# main.net
KiCad netlist of a schematic drawn in Altium Designer
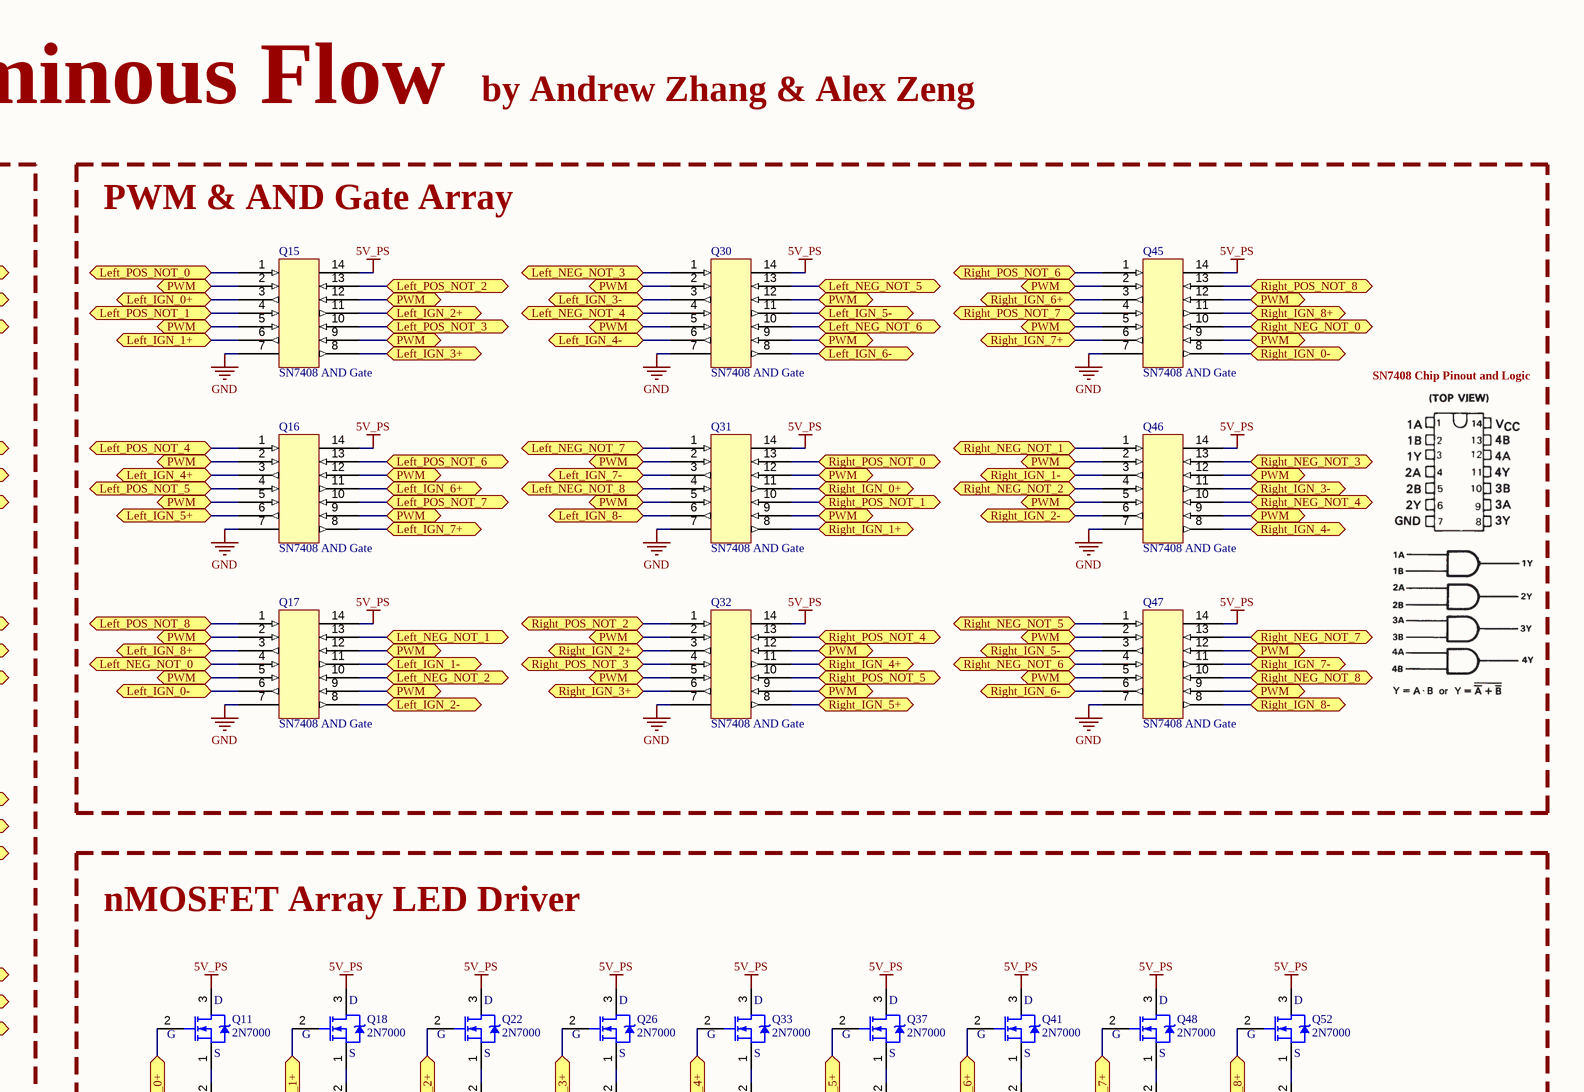
[diagram p0: main.SchDoc, top right]
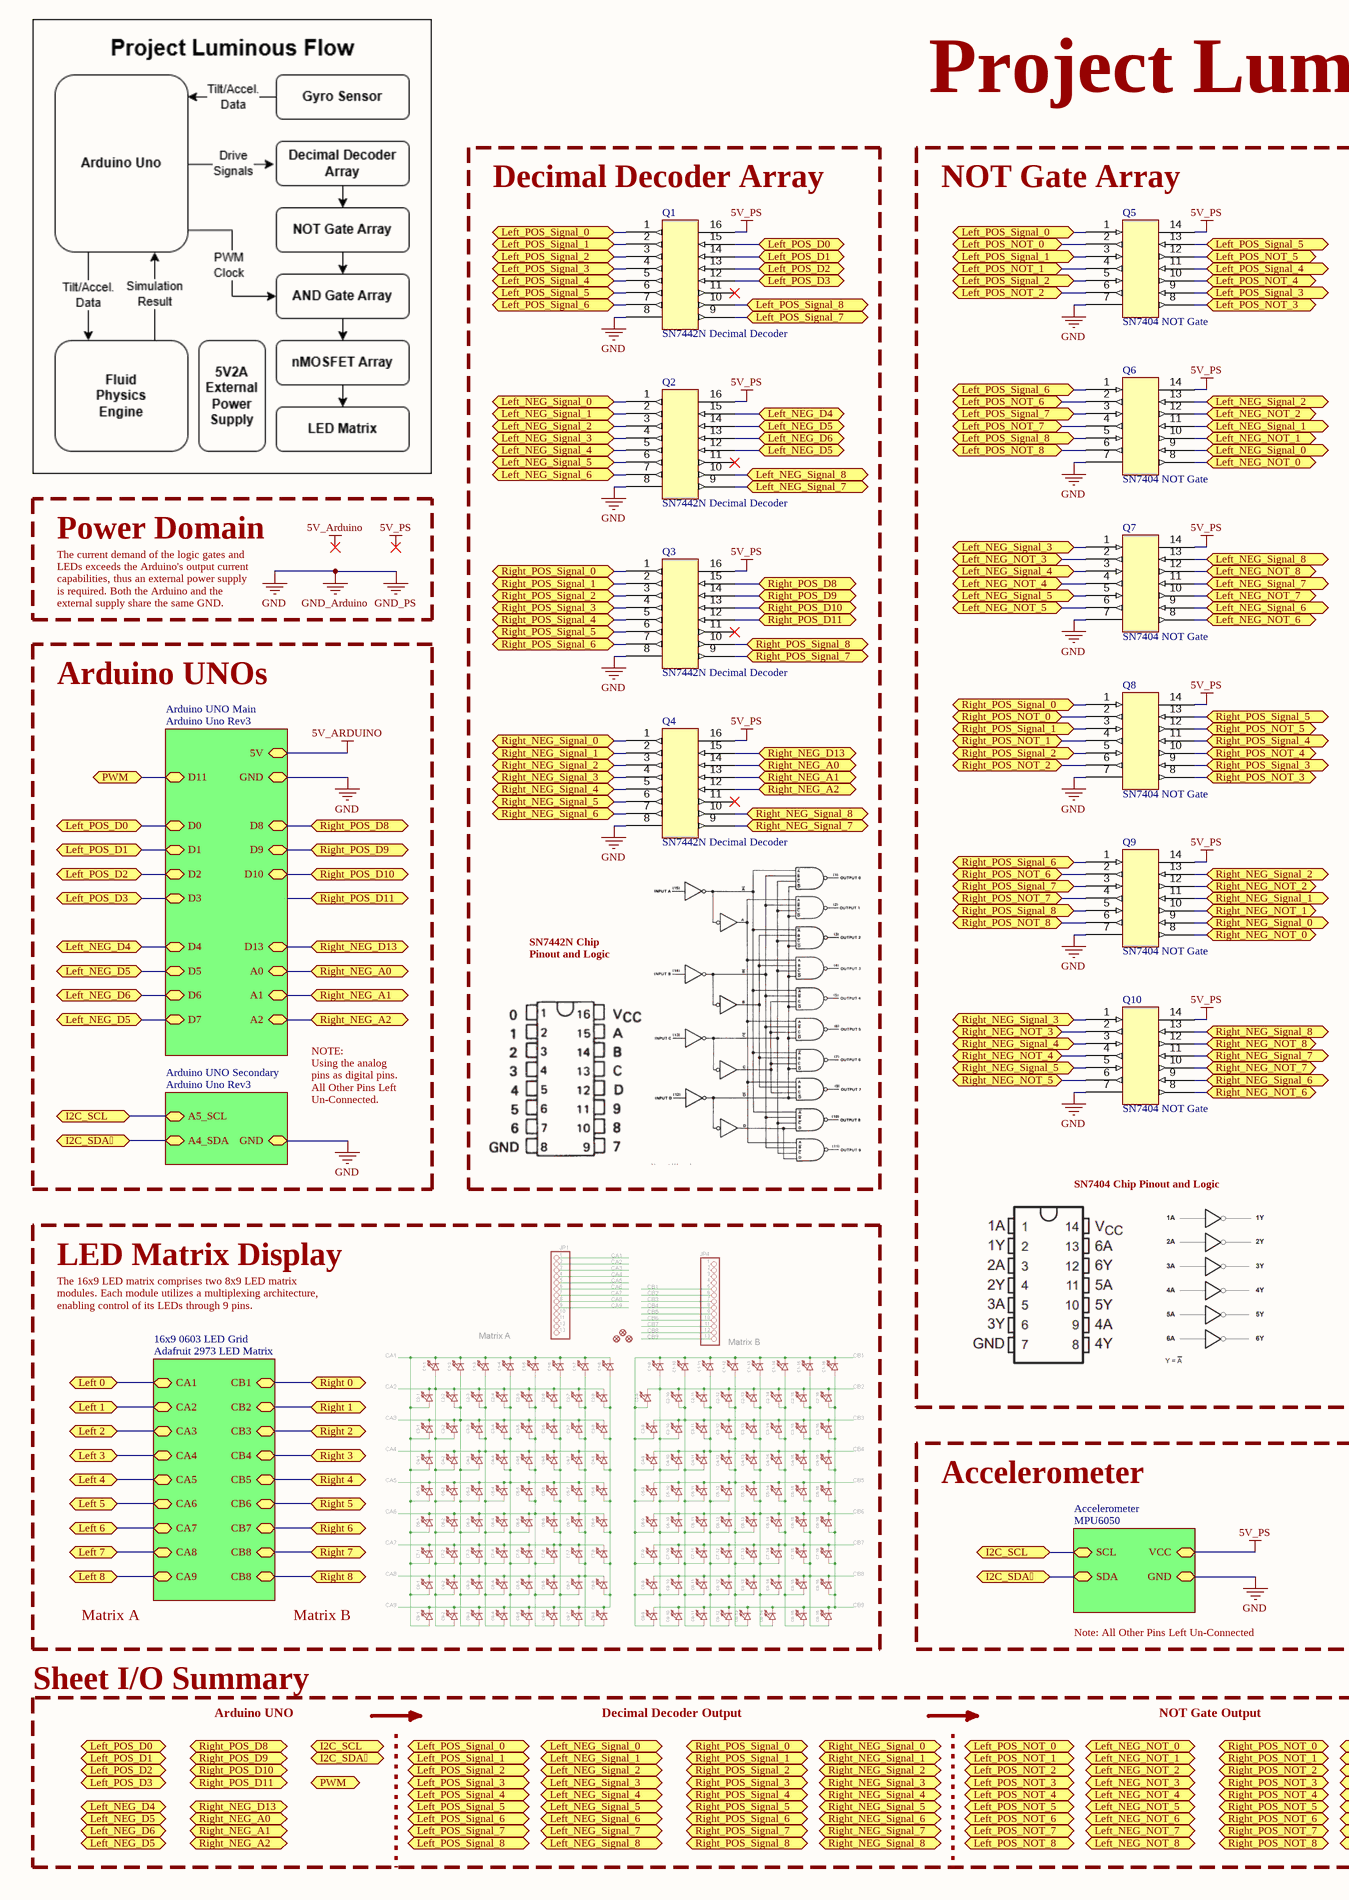
[diagram p1: main.SchDoc, bottom left]
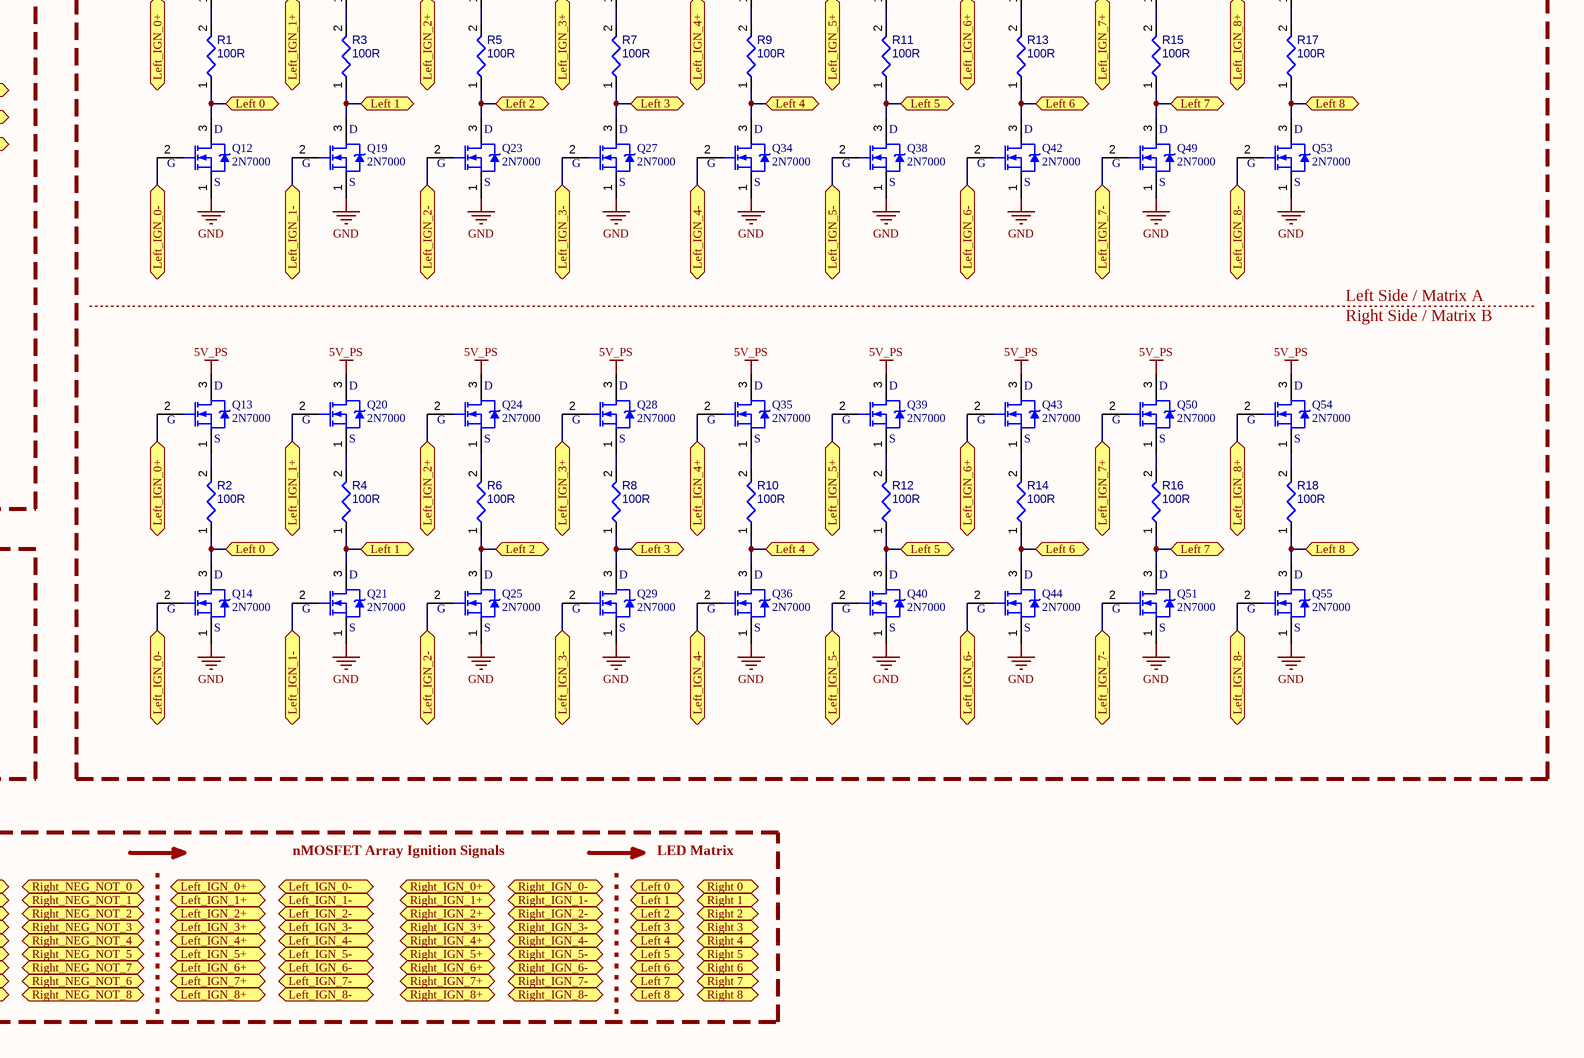
[diagram p2: main.SchDoc, bottom right]

(export (version "E")
  (design (tool "Eeschema 10.0.6"))
  (components
    (comp (ref "Q1")
      (value "SN7442N Decimal Decoder")
      (description "10-line Decimal Decoder")
      (libsource (lib "OTGRP") (part "SN7442N"))
    )
    (comp (ref "Q2")
      (value "SN7442N Decimal Decoder")
      (description "10-line Decimal Decoder")
      (libsource (lib "OTGRP") (part "SN7442N"))
    )
    (comp (ref "Q3")
      (value "SN7442N Decimal Decoder")
      (description "10-line Decimal Decoder")
      (libsource (lib "OTGRP") (part "SN7442N"))
    )
    (comp (ref "Q4")
      (value "SN7442N Decimal Decoder")
      (description "10-line Decimal Decoder")
      (libsource (lib "OTGRP") (part "SN7442N"))
    )
    (comp (ref "Q5") (value "SN7404 NOT Gate") (libsource (lib "OTGRP") (part "SN7404 NOT Gate")))
    (comp (ref "Q6") (value "SN7404 NOT Gate") (libsource (lib "OTGRP") (part "SN7404 NOT Gate")))
    (comp (ref "Q7") (value "SN7404 NOT Gate") (libsource (lib "OTGRP") (part "SN7404 NOT Gate")))
    (comp (ref "Q8") (value "SN7404 NOT Gate") (libsource (lib "OTGRP") (part "SN7404 NOT Gate")))
    (comp (ref "Q9") (value "SN7404 NOT Gate") (libsource (lib "OTGRP") (part "SN7404 NOT Gate")))
    (comp (ref "Q10") (value "SN7404 NOT Gate") (libsource (lib "OTGRP") (part "SN7404 NOT Gate")))
    (comp (ref "Q11")
      (value "2N7000")
      (footprint "ONSC-TO-92-3-29-11_AM_BL")
      (description "Small Signal MOSFET, 200 mA, 60 V, N-Channel, 3-Pin TO-92, Bulk Box")
      (fields (field (name "POWER") "400mW") (field (name "MANUFACTURER") "Fairchild Semiconductor"))
      (libsource (lib "OTGRP") (part "ONSC-NMOS-S1G2D3-3"))
    )
    (comp (ref "Q12")
      (value "2N7000")
      (footprint "ONSC-TO-92-3-29-11_AM_BL")
      (description "Small Signal MOSFET, 200 mA, 60 V, N-Channel, 3-Pin TO-92, Bulk Box")
      (fields (field (name "POWER") "400mW") (field (name "MANUFACTURER") "Fairchild Semiconductor"))
      (libsource (lib "OTGRP") (part "ONSC-NMOS-S1G2D3-3"))
    )
    (comp (ref "Q13")
      (value "2N7000")
      (footprint "ONSC-TO-92-3-29-11_AM_BL")
      (description "Small Signal MOSFET, 200 mA, 60 V, N-Channel, 3-Pin TO-92, Bulk Box")
      (fields (field (name "POWER") "400mW") (field (name "MANUFACTURER") "Fairchild Semiconductor"))
      (libsource (lib "OTGRP") (part "ONSC-NMOS-S1G2D3-3"))
    )
    (comp (ref "Q14")
      (value "2N7000")
      (footprint "ONSC-TO-92-3-29-11_AM_BL")
      (description "Small Signal MOSFET, 200 mA, 60 V, N-Channel, 3-Pin TO-92, Bulk Box")
      (fields (field (name "POWER") "400mW") (field (name "MANUFACTURER") "Fairchild Semiconductor"))
      (libsource (lib "OTGRP") (part "ONSC-NMOS-S1G2D3-3"))
    )
    (comp (ref "Q15")
      (value "SN7408 AND Gate")
      (description "Quad 2-input Positive-AND gates 14-PDIP 0 to 70")
      (libsource (lib "OTGRP") (part "SN7408"))
    )
    (comp (ref "Q16")
      (value "SN7408 AND Gate")
      (description "Quad 2-input Positive-AND gates 14-PDIP 0 to 70")
      (libsource (lib "OTGRP") (part "SN7408"))
    )
    (comp (ref "Q17")
      (value "SN7408 AND Gate")
      (description "Quad 2-input Positive-AND gates 14-PDIP 0 to 70")
      (libsource (lib "OTGRP") (part "SN7408"))
    )
    (comp (ref "Q18")
      (value "2N7000")
      (footprint "ONSC-TO-92-3-29-11_AM_BL")
      (description "Small Signal MOSFET, 200 mA, 60 V, N-Channel, 3-Pin TO-92, Bulk Box")
      (fields (field (name "POWER") "400mW") (field (name "MANUFACTURER") "Fairchild Semiconductor"))
      (libsource (lib "OTGRP") (part "ONSC-NMOS-S1G2D3-3"))
    )
    (comp (ref "Q19")
      (value "2N7000")
      (footprint "ONSC-TO-92-3-29-11_AM_BL")
      (description "Small Signal MOSFET, 200 mA, 60 V, N-Channel, 3-Pin TO-92, Bulk Box")
      (fields (field (name "POWER") "400mW") (field (name "MANUFACTURER") "Fairchild Semiconductor"))
      (libsource (lib "OTGRP") (part "ONSC-NMOS-S1G2D3-3"))
    )
    (comp (ref "Q20")
      (value "2N7000")
      (footprint "ONSC-TO-92-3-29-11_AM_BL")
      (description "Small Signal MOSFET, 200 mA, 60 V, N-Channel, 3-Pin TO-92, Bulk Box")
      (fields (field (name "POWER") "400mW") (field (name "MANUFACTURER") "Fairchild Semiconductor"))
      (libsource (lib "OTGRP") (part "ONSC-NMOS-S1G2D3-3"))
    )
    (comp (ref "Q21")
      (value "2N7000")
      (footprint "ONSC-TO-92-3-29-11_AM_BL")
      (description "Small Signal MOSFET, 200 mA, 60 V, N-Channel, 3-Pin TO-92, Bulk Box")
      (fields (field (name "POWER") "400mW") (field (name "MANUFACTURER") "Fairchild Semiconductor"))
      (libsource (lib "OTGRP") (part "ONSC-NMOS-S1G2D3-3"))
    )
    (comp (ref "Q22")
      (value "2N7000")
      (footprint "ONSC-TO-92-3-29-11_AM_BL")
      (description "Small Signal MOSFET, 200 mA, 60 V, N-Channel, 3-Pin TO-92, Bulk Box")
      (fields (field (name "POWER") "400mW") (field (name "MANUFACTURER") "Fairchild Semiconductor"))
      (libsource (lib "OTGRP") (part "ONSC-NMOS-S1G2D3-3"))
    )
    (comp (ref "Q23")
      (value "2N7000")
      (footprint "ONSC-TO-92-3-29-11_AM_BL")
      (description "Small Signal MOSFET, 200 mA, 60 V, N-Channel, 3-Pin TO-92, Bulk Box")
      (fields (field (name "POWER") "400mW") (field (name "MANUFACTURER") "Fairchild Semiconductor"))
      (libsource (lib "OTGRP") (part "ONSC-NMOS-S1G2D3-3"))
    )
    (comp (ref "Q24")
      (value "2N7000")
      (footprint "ONSC-TO-92-3-29-11_AM_BL")
      (description "Small Signal MOSFET, 200 mA, 60 V, N-Channel, 3-Pin TO-92, Bulk Box")
      (fields (field (name "POWER") "400mW") (field (name "MANUFACTURER") "Fairchild Semiconductor"))
      (libsource (lib "OTGRP") (part "ONSC-NMOS-S1G2D3-3"))
    )
    (comp (ref "Q25")
      (value "2N7000")
      (footprint "ONSC-TO-92-3-29-11_AM_BL")
      (description "Small Signal MOSFET, 200 mA, 60 V, N-Channel, 3-Pin TO-92, Bulk Box")
      (fields (field (name "POWER") "400mW") (field (name "MANUFACTURER") "Fairchild Semiconductor"))
      (libsource (lib "OTGRP") (part "ONSC-NMOS-S1G2D3-3"))
    )
    (comp (ref "Q26")
      (value "2N7000")
      (footprint "ONSC-TO-92-3-29-11_AM_BL")
      (description "Small Signal MOSFET, 200 mA, 60 V, N-Channel, 3-Pin TO-92, Bulk Box")
      (fields (field (name "POWER") "400mW") (field (name "MANUFACTURER") "Fairchild Semiconductor"))
      (libsource (lib "OTGRP") (part "ONSC-NMOS-S1G2D3-3"))
    )
    (comp (ref "Q27")
      (value "2N7000")
      (footprint "ONSC-TO-92-3-29-11_AM_BL")
      (description "Small Signal MOSFET, 200 mA, 60 V, N-Channel, 3-Pin TO-92, Bulk Box")
      (fields (field (name "POWER") "400mW") (field (name "MANUFACTURER") "Fairchild Semiconductor"))
      (libsource (lib "OTGRP") (part "ONSC-NMOS-S1G2D3-3"))
    )
    (comp (ref "Q28")
      (value "2N7000")
      (footprint "ONSC-TO-92-3-29-11_AM_BL")
      (description "Small Signal MOSFET, 200 mA, 60 V, N-Channel, 3-Pin TO-92, Bulk Box")
      (fields (field (name "POWER") "400mW") (field (name "MANUFACTURER") "Fairchild Semiconductor"))
      (libsource (lib "OTGRP") (part "ONSC-NMOS-S1G2D3-3"))
    )
    (comp (ref "Q29")
      (value "2N7000")
      (footprint "ONSC-TO-92-3-29-11_AM_BL")
      (description "Small Signal MOSFET, 200 mA, 60 V, N-Channel, 3-Pin TO-92, Bulk Box")
      (fields (field (name "POWER") "400mW") (field (name "MANUFACTURER") "Fairchild Semiconductor"))
      (libsource (lib "OTGRP") (part "ONSC-NMOS-S1G2D3-3"))
    )
    (comp (ref "Q30")
      (value "SN7408 AND Gate")
      (description "Quad 2-input Positive-AND gates 14-PDIP 0 to 70")
      (libsource (lib "OTGRP") (part "SN7408"))
    )
    (comp (ref "Q31")
      (value "SN7408 AND Gate")
      (description "Quad 2-input Positive-AND gates 14-PDIP 0 to 70")
      (libsource (lib "OTGRP") (part "SN7408"))
    )
    (comp (ref "Q32")
      (value "SN7408 AND Gate")
      (description "Quad 2-input Positive-AND gates 14-PDIP 0 to 70")
      (libsource (lib "OTGRP") (part "SN7408"))
    )
    (comp (ref "Q33")
      (value "2N7000")
      (footprint "ONSC-TO-92-3-29-11_AM_BL")
      (description "Small Signal MOSFET, 200 mA, 60 V, N-Channel, 3-Pin TO-92, Bulk Box")
      (fields (field (name "POWER") "400mW") (field (name "MANUFACTURER") "Fairchild Semiconductor"))
      (libsource (lib "OTGRP") (part "ONSC-NMOS-S1G2D3-3"))
    )
    (comp (ref "Q34")
      (value "2N7000")
      (footprint "ONSC-TO-92-3-29-11_AM_BL")
      (description "Small Signal MOSFET, 200 mA, 60 V, N-Channel, 3-Pin TO-92, Bulk Box")
      (fields (field (name "POWER") "400mW") (field (name "MANUFACTURER") "Fairchild Semiconductor"))
      (libsource (lib "OTGRP") (part "ONSC-NMOS-S1G2D3-3"))
    )
    (comp (ref "Q35")
      (value "2N7000")
      (footprint "ONSC-TO-92-3-29-11_AM_BL")
      (description "Small Signal MOSFET, 200 mA, 60 V, N-Channel, 3-Pin TO-92, Bulk Box")
      (fields (field (name "POWER") "400mW") (field (name "MANUFACTURER") "Fairchild Semiconductor"))
      (libsource (lib "OTGRP") (part "ONSC-NMOS-S1G2D3-3"))
    )
    (comp (ref "Q36")
      (value "2N7000")
      (footprint "ONSC-TO-92-3-29-11_AM_BL")
      (description "Small Signal MOSFET, 200 mA, 60 V, N-Channel, 3-Pin TO-92, Bulk Box")
      (fields (field (name "POWER") "400mW") (field (name "MANUFACTURER") "Fairchild Semiconductor"))
      (libsource (lib "OTGRP") (part "ONSC-NMOS-S1G2D3-3"))
    )
    (comp (ref "Q37")
      (value "2N7000")
      (footprint "ONSC-TO-92-3-29-11_AM_BL")
      (description "Small Signal MOSFET, 200 mA, 60 V, N-Channel, 3-Pin TO-92, Bulk Box")
      (fields (field (name "POWER") "400mW") (field (name "MANUFACTURER") "Fairchild Semiconductor"))
      (libsource (lib "OTGRP") (part "ONSC-NMOS-S1G2D3-3"))
    )
    (comp (ref "Q38")
      (value "2N7000")
      (footprint "ONSC-TO-92-3-29-11_AM_BL")
      (description "Small Signal MOSFET, 200 mA, 60 V, N-Channel, 3-Pin TO-92, Bulk Box")
      (fields (field (name "POWER") "400mW") (field (name "MANUFACTURER") "Fairchild Semiconductor"))
      (libsource (lib "OTGRP") (part "ONSC-NMOS-S1G2D3-3"))
    )
    (comp (ref "Q39")
      (value "2N7000")
      (footprint "ONSC-TO-92-3-29-11_AM_BL")
      (description "Small Signal MOSFET, 200 mA, 60 V, N-Channel, 3-Pin TO-92, Bulk Box")
      (fields (field (name "POWER") "400mW") (field (name "MANUFACTURER") "Fairchild Semiconductor"))
      (libsource (lib "OTGRP") (part "ONSC-NMOS-S1G2D3-3"))
    )
    (comp (ref "Q40")
      (value "2N7000")
      (footprint "ONSC-TO-92-3-29-11_AM_BL")
      (description "Small Signal MOSFET, 200 mA, 60 V, N-Channel, 3-Pin TO-92, Bulk Box")
      (fields (field (name "POWER") "400mW") (field (name "MANUFACTURER") "Fairchild Semiconductor"))
      (libsource (lib "OTGRP") (part "ONSC-NMOS-S1G2D3-3"))
    )
    (comp (ref "Q41")
      (value "2N7000")
      (footprint "ONSC-TO-92-3-29-11_AM_BL")
      (description "Small Signal MOSFET, 200 mA, 60 V, N-Channel, 3-Pin TO-92, Bulk Box")
      (fields (field (name "POWER") "400mW") (field (name "MANUFACTURER") "Fairchild Semiconductor"))
      (libsource (lib "OTGRP") (part "ONSC-NMOS-S1G2D3-3"))
    )
    (comp (ref "Q42")
      (value "2N7000")
      (footprint "ONSC-TO-92-3-29-11_AM_BL")
      (description "Small Signal MOSFET, 200 mA, 60 V, N-Channel, 3-Pin TO-92, Bulk Box")
      (fields (field (name "POWER") "400mW") (field (name "MANUFACTURER") "Fairchild Semiconductor"))
      (libsource (lib "OTGRP") (part "ONSC-NMOS-S1G2D3-3"))
    )
    (comp (ref "Q43")
      (value "2N7000")
      (footprint "ONSC-TO-92-3-29-11_AM_BL")
      (description "Small Signal MOSFET, 200 mA, 60 V, N-Channel, 3-Pin TO-92, Bulk Box")
      (fields (field (name "POWER") "400mW") (field (name "MANUFACTURER") "Fairchild Semiconductor"))
      (libsource (lib "OTGRP") (part "ONSC-NMOS-S1G2D3-3"))
    )
    (comp (ref "Q44")
      (value "2N7000")
      (footprint "ONSC-TO-92-3-29-11_AM_BL")
      (description "Small Signal MOSFET, 200 mA, 60 V, N-Channel, 3-Pin TO-92, Bulk Box")
      (fields (field (name "POWER") "400mW") (field (name "MANUFACTURER") "Fairchild Semiconductor"))
      (libsource (lib "OTGRP") (part "ONSC-NMOS-S1G2D3-3"))
    )
    (comp (ref "Q45")
      (value "SN7408 AND Gate")
      (description "Quad 2-input Positive-AND gates 14-PDIP 0 to 70")
      (libsource (lib "OTGRP") (part "SN7408"))
    )
    (comp (ref "Q46")
      (value "SN7408 AND Gate")
      (description "Quad 2-input Positive-AND gates 14-PDIP 0 to 70")
      (libsource (lib "OTGRP") (part "SN7408"))
    )
    (comp (ref "Q47")
      (value "SN7408 AND Gate")
      (description "Quad 2-input Positive-AND gates 14-PDIP 0 to 70")
      (libsource (lib "OTGRP") (part "SN7408"))
    )
    (comp (ref "Q48")
      (value "2N7000")
      (footprint "ONSC-TO-92-3-29-11_AM_BL")
      (description "Small Signal MOSFET, 200 mA, 60 V, N-Channel, 3-Pin TO-92, Bulk Box")
      (fields (field (name "POWER") "400mW") (field (name "MANUFACTURER") "Fairchild Semiconductor"))
      (libsource (lib "OTGRP") (part "ONSC-NMOS-S1G2D3-3"))
    )
    (comp (ref "Q49")
      (value "2N7000")
      (footprint "ONSC-TO-92-3-29-11_AM_BL")
      (description "Small Signal MOSFET, 200 mA, 60 V, N-Channel, 3-Pin TO-92, Bulk Box")
      (fields (field (name "POWER") "400mW") (field (name "MANUFACTURER") "Fairchild Semiconductor"))
      (libsource (lib "OTGRP") (part "ONSC-NMOS-S1G2D3-3"))
    )
    (comp (ref "Q50")
      (value "2N7000")
      (footprint "ONSC-TO-92-3-29-11_AM_BL")
      (description "Small Signal MOSFET, 200 mA, 60 V, N-Channel, 3-Pin TO-92, Bulk Box")
      (fields (field (name "POWER") "400mW") (field (name "MANUFACTURER") "Fairchild Semiconductor"))
      (libsource (lib "OTGRP") (part "ONSC-NMOS-S1G2D3-3"))
    )
    (comp (ref "Q51")
      (value "2N7000")
      (footprint "ONSC-TO-92-3-29-11_AM_BL")
      (description "Small Signal MOSFET, 200 mA, 60 V, N-Channel, 3-Pin TO-92, Bulk Box")
      (fields (field (name "POWER") "400mW") (field (name "MANUFACTURER") "Fairchild Semiconductor"))
      (libsource (lib "OTGRP") (part "ONSC-NMOS-S1G2D3-3"))
    )
    (comp (ref "Q52")
      (value "2N7000")
      (footprint "ONSC-TO-92-3-29-11_AM_BL")
      (description "Small Signal MOSFET, 200 mA, 60 V, N-Channel, 3-Pin TO-92, Bulk Box")
      (fields (field (name "POWER") "400mW") (field (name "MANUFACTURER") "Fairchild Semiconductor"))
      (libsource (lib "OTGRP") (part "ONSC-NMOS-S1G2D3-3"))
    )
    (comp (ref "Q53")
      (value "2N7000")
      (footprint "ONSC-TO-92-3-29-11_AM_BL")
      (description "Small Signal MOSFET, 200 mA, 60 V, N-Channel, 3-Pin TO-92, Bulk Box")
      (fields (field (name "POWER") "400mW") (field (name "MANUFACTURER") "Fairchild Semiconductor"))
      (libsource (lib "OTGRP") (part "ONSC-NMOS-S1G2D3-3"))
    )
    (comp (ref "Q54")
      (value "2N7000")
      (footprint "ONSC-TO-92-3-29-11_AM_BL")
      (description "Small Signal MOSFET, 200 mA, 60 V, N-Channel, 3-Pin TO-92, Bulk Box")
      (fields (field (name "POWER") "400mW") (field (name "MANUFACTURER") "Fairchild Semiconductor"))
      (libsource (lib "OTGRP") (part "ONSC-NMOS-S1G2D3-3"))
    )
    (comp (ref "Q55")
      (value "2N7000")
      (footprint "ONSC-TO-92-3-29-11_AM_BL")
      (description "Small Signal MOSFET, 200 mA, 60 V, N-Channel, 3-Pin TO-92, Bulk Box")
      (fields (field (name "POWER") "400mW") (field (name "MANUFACTURER") "Fairchild Semiconductor"))
      (libsource (lib "OTGRP") (part "ONSC-NMOS-S1G2D3-3"))
    )
    (comp (ref "R1")
      (value "100R")
      (footprint "RESC0402(1005)_L")
      (fields (field (name "TOLERANCE") "1%") (field (name "POWER") "63mW"))
      (libsource (lib "OTGRP") (part "100R2F"))
    )
    (comp (ref "R2")
      (value "100R")
      (footprint "RESC0402(1005)_L")
      (fields (field (name "TOLERANCE") "1%") (field (name "POWER") "63mW"))
      (libsource (lib "OTGRP") (part "100R2F"))
    )
    (comp (ref "R3")
      (value "100R")
      (footprint "RESC0402(1005)_L")
      (fields (field (name "TOLERANCE") "1%") (field (name "POWER") "63mW"))
      (libsource (lib "OTGRP") (part "100R2F"))
    )
    (comp (ref "R4")
      (value "100R")
      (footprint "RESC0402(1005)_L")
      (fields (field (name "TOLERANCE") "1%") (field (name "POWER") "63mW"))
      (libsource (lib "OTGRP") (part "100R2F"))
    )
    (comp (ref "R5")
      (value "100R")
      (footprint "RESC0402(1005)_L")
      (fields (field (name "TOLERANCE") "1%") (field (name "POWER") "63mW"))
      (libsource (lib "OTGRP") (part "100R2F"))
    )
    (comp (ref "R6")
      (value "100R")
      (footprint "RESC0402(1005)_L")
      (fields (field (name "TOLERANCE") "1%") (field (name "POWER") "63mW"))
      (libsource (lib "OTGRP") (part "100R2F"))
    )
    (comp (ref "R7")
      (value "100R")
      (footprint "RESC0402(1005)_L")
      (fields (field (name "TOLERANCE") "1%") (field (name "POWER") "63mW"))
      (libsource (lib "OTGRP") (part "100R2F"))
    )
    (comp (ref "R8")
      (value "100R")
      (footprint "RESC0402(1005)_L")
      (fields (field (name "TOLERANCE") "1%") (field (name "POWER") "63mW"))
      (libsource (lib "OTGRP") (part "100R2F"))
    )
    (comp (ref "R9")
      (value "100R")
      (footprint "RESC0402(1005)_L")
      (fields (field (name "TOLERANCE") "1%") (field (name "POWER") "63mW"))
      (libsource (lib "OTGRP") (part "100R2F"))
    )
    (comp (ref "R10")
      (value "100R")
      (footprint "RESC0402(1005)_L")
      (fields (field (name "TOLERANCE") "1%") (field (name "POWER") "63mW"))
      (libsource (lib "OTGRP") (part "100R2F"))
    )
    (comp (ref "R11")
      (value "100R")
      (footprint "RESC0402(1005)_L")
      (fields (field (name "TOLERANCE") "1%") (field (name "POWER") "63mW"))
      (libsource (lib "OTGRP") (part "100R2F"))
    )
    (comp (ref "R12")
      (value "100R")
      (footprint "RESC0402(1005)_L")
      (fields (field (name "TOLERANCE") "1%") (field (name "POWER") "63mW"))
      (libsource (lib "OTGRP") (part "100R2F"))
    )
    (comp (ref "R13")
      (value "100R")
      (footprint "RESC0402(1005)_L")
      (fields (field (name "TOLERANCE") "1%") (field (name "POWER") "63mW"))
      (libsource (lib "OTGRP") (part "100R2F"))
    )
    (comp (ref "R14")
      (value "100R")
      (footprint "RESC0402(1005)_L")
      (fields (field (name "TOLERANCE") "1%") (field (name "POWER") "63mW"))
      (libsource (lib "OTGRP") (part "100R2F"))
    )
    (comp (ref "R15")
      (value "100R")
      (footprint "RESC0402(1005)_L")
      (fields (field (name "TOLERANCE") "1%") (field (name "POWER") "63mW"))
      (libsource (lib "OTGRP") (part "100R2F"))
    )
    (comp (ref "R16")
      (value "100R")
      (footprint "RESC0402(1005)_L")
      (fields (field (name "TOLERANCE") "1%") (field (name "POWER") "63mW"))
      (libsource (lib "OTGRP") (part "100R2F"))
    )
    (comp (ref "R17")
      (value "100R")
      (footprint "RESC0402(1005)_L")
      (fields (field (name "TOLERANCE") "1%") (field (name "POWER") "63mW"))
      (libsource (lib "OTGRP") (part "100R2F"))
    )
    (comp (ref "R18")
      (value "100R")
      (footprint "RESC0402(1005)_L")
      (fields (field (name "TOLERANCE") "1%") (field (name "POWER") "63mW"))
      (libsource (lib "OTGRP") (part "100R2F"))
    )
  )
  (nets
    (net (code "3") (name "/Left 0") (class "Default")
      (node (ref "Q12") (pin "3") (pinfunction "D_3") (pintype "passive"))
      (node (ref "Q14") (pin "3") (pinfunction "D_3") (pintype "passive"))
      (node (ref "R1") (pin "1") (pinfunction "1_1") (pintype "passive"))
      (node (ref "R2") (pin "1") (pinfunction "1_1") (pintype "passive"))
    )
    (net (code "4") (name "/Left 1") (class "Default")
      (node (ref "Q19") (pin "3") (pinfunction "D_3") (pintype "passive"))
      (node (ref "Q21") (pin "3") (pinfunction "D_3") (pintype "passive"))
      (node (ref "R3") (pin "1") (pinfunction "1_1") (pintype "passive"))
      (node (ref "R4") (pin "1") (pinfunction "1_1") (pintype "passive"))
    )
    (net (code "5") (name "/Left 2") (class "Default")
      (node (ref "Q23") (pin "3") (pinfunction "D_3") (pintype "passive"))
      (node (ref "Q25") (pin "3") (pinfunction "D_3") (pintype "passive"))
      (node (ref "R5") (pin "1") (pinfunction "1_1") (pintype "passive"))
      (node (ref "R6") (pin "1") (pinfunction "1_1") (pintype "passive"))
    )
    (net (code "6") (name "/Left 3") (class "Default")
      (node (ref "Q27") (pin "3") (pinfunction "D_3") (pintype "passive"))
      (node (ref "Q29") (pin "3") (pinfunction "D_3") (pintype "passive"))
      (node (ref "R7") (pin "1") (pinfunction "1_1") (pintype "passive"))
      (node (ref "R8") (pin "1") (pinfunction "1_1") (pintype "passive"))
    )
    (net (code "7") (name "/Left 4") (class "Default")
      (node (ref "Q34") (pin "3") (pinfunction "D_3") (pintype "passive"))
      (node (ref "Q36") (pin "3") (pinfunction "D_3") (pintype "passive"))
      (node (ref "R10") (pin "1") (pinfunction "1_1") (pintype "passive"))
      (node (ref "R9") (pin "1") (pinfunction "1_1") (pintype "passive"))
    )
    (net (code "8") (name "/Left 5") (class "Default")
      (node (ref "Q38") (pin "3") (pinfunction "D_3") (pintype "passive"))
      (node (ref "Q40") (pin "3") (pinfunction "D_3") (pintype "passive"))
      (node (ref "R11") (pin "1") (pinfunction "1_1") (pintype "passive"))
      (node (ref "R12") (pin "1") (pinfunction "1_1") (pintype "passive"))
    )
    (net (code "9") (name "/Left 6") (class "Default")
      (node (ref "Q42") (pin "3") (pinfunction "D_3") (pintype "passive"))
      (node (ref "Q44") (pin "3") (pinfunction "D_3") (pintype "passive"))
      (node (ref "R13") (pin "1") (pinfunction "1_1") (pintype "passive"))
      (node (ref "R14") (pin "1") (pinfunction "1_1") (pintype "passive"))
    )
    (net (code "10") (name "/Left 7") (class "Default")
      (node (ref "Q49") (pin "3") (pinfunction "D_3") (pintype "passive"))
      (node (ref "Q51") (pin "3") (pinfunction "D_3") (pintype "passive"))
      (node (ref "R15") (pin "1") (pinfunction "1_1") (pintype "passive"))
      (node (ref "R16") (pin "1") (pinfunction "1_1") (pintype "passive"))
    )
    (net (code "11") (name "/Left 8") (class "Default")
      (node (ref "Q53") (pin "3") (pinfunction "D_3") (pintype "passive"))
      (node (ref "Q55") (pin "3") (pinfunction "D_3") (pintype "passive"))
      (node (ref "R17") (pin "1") (pinfunction "1_1") (pintype "passive"))
      (node (ref "R18") (pin "1") (pinfunction "1_1") (pintype "passive"))
    )
    (net (code "12") (name "/Left_IGN_0+") (class "Default")
      (node (ref "Q11") (pin "2") (pinfunction "G_2") (pintype "passive"))
      (node (ref "Q13") (pin "2") (pinfunction "G_2") (pintype "passive"))
      (node (ref "Q15") (pin "3") (pintype "output"))
    )
    (net (code "13") (name "/Left_IGN_0-") (class "Default")
      (node (ref "Q12") (pin "2") (pinfunction "G_2") (pintype "passive"))
      (node (ref "Q14") (pin "2") (pinfunction "G_2") (pintype "passive"))
      (node (ref "Q17") (pin "6") (pintype "output"))
    )
    (net (code "14") (name "/Left_IGN_1+") (class "Default")
      (node (ref "Q15") (pin "6") (pintype "output"))
      (node (ref "Q18") (pin "2") (pinfunction "G_2") (pintype "passive"))
      (node (ref "Q20") (pin "2") (pinfunction "G_2") (pintype "passive"))
    )
    (net (code "15") (name "/Left_IGN_1-") (class "Default")
      (node (ref "Q17") (pin "11") (pintype "output"))
      (node (ref "Q19") (pin "2") (pinfunction "G_2") (pintype "passive"))
      (node (ref "Q21") (pin "2") (pinfunction "G_2") (pintype "passive"))
    )
    (net (code "16") (name "/Left_IGN_2+") (class "Default")
      (node (ref "Q15") (pin "11") (pintype "output"))
      (node (ref "Q22") (pin "2") (pinfunction "G_2") (pintype "passive"))
      (node (ref "Q24") (pin "2") (pinfunction "G_2") (pintype "passive"))
    )
    (net (code "17") (name "/Left_IGN_2-") (class "Default")
      (node (ref "Q17") (pin "8") (pintype "output"))
      (node (ref "Q23") (pin "2") (pinfunction "G_2") (pintype "passive"))
      (node (ref "Q25") (pin "2") (pinfunction "G_2") (pintype "passive"))
    )
    (net (code "18") (name "/Left_IGN_3+") (class "Default")
      (node (ref "Q15") (pin "8") (pintype "output"))
      (node (ref "Q26") (pin "2") (pinfunction "G_2") (pintype "passive"))
      (node (ref "Q28") (pin "2") (pinfunction "G_2") (pintype "passive"))
    )
    (net (code "19") (name "/Left_IGN_3-") (class "Default")
      (node (ref "Q27") (pin "2") (pinfunction "G_2") (pintype "passive"))
      (node (ref "Q29") (pin "2") (pinfunction "G_2") (pintype "passive"))
      (node (ref "Q30") (pin "3") (pintype "output"))
    )
    (net (code "20") (name "/Left_IGN_4+") (class "Default")
      (node (ref "Q16") (pin "3") (pintype "output"))
      (node (ref "Q33") (pin "2") (pinfunction "G_2") (pintype "passive"))
      (node (ref "Q35") (pin "2") (pinfunction "G_2") (pintype "passive"))
    )
    (net (code "21") (name "/Left_IGN_4-") (class "Default")
      (node (ref "Q30") (pin "6") (pintype "output"))
      (node (ref "Q34") (pin "2") (pinfunction "G_2") (pintype "passive"))
      (node (ref "Q36") (pin "2") (pinfunction "G_2") (pintype "passive"))
    )
    (net (code "22") (name "/Left_IGN_5+") (class "Default")
      (node (ref "Q16") (pin "6") (pintype "output"))
      (node (ref "Q37") (pin "2") (pinfunction "G_2") (pintype "passive"))
      (node (ref "Q39") (pin "2") (pinfunction "G_2") (pintype "passive"))
    )
    (net (code "23") (name "/Left_IGN_5-") (class "Default")
      (node (ref "Q30") (pin "11") (pintype "output"))
      (node (ref "Q38") (pin "2") (pinfunction "G_2") (pintype "passive"))
      (node (ref "Q40") (pin "2") (pinfunction "G_2") (pintype "passive"))
    )
    (net (code "24") (name "/Left_IGN_6+") (class "Default")
      (node (ref "Q16") (pin "11") (pintype "output"))
      (node (ref "Q41") (pin "2") (pinfunction "G_2") (pintype "passive"))
      (node (ref "Q43") (pin "2") (pinfunction "G_2") (pintype "passive"))
    )
    (net (code "25") (name "/Left_IGN_6-") (class "Default")
      (node (ref "Q30") (pin "8") (pintype "output"))
      (node (ref "Q42") (pin "2") (pinfunction "G_2") (pintype "passive"))
      (node (ref "Q44") (pin "2") (pinfunction "G_2") (pintype "passive"))
    )
    (net (code "26") (name "/Left_IGN_7+") (class "Default")
      (node (ref "Q16") (pin "8") (pintype "output"))
      (node (ref "Q48") (pin "2") (pinfunction "G_2") (pintype "passive"))
      (node (ref "Q50") (pin "2") (pinfunction "G_2") (pintype "passive"))
    )
    (net (code "27") (name "/Left_IGN_7-") (class "Default")
      (node (ref "Q31") (pin "3") (pintype "output"))
      (node (ref "Q49") (pin "2") (pinfunction "G_2") (pintype "passive"))
      (node (ref "Q51") (pin "2") (pinfunction "G_2") (pintype "passive"))
    )
    (net (code "28") (name "/Left_IGN_8+") (class "Default")
      (node (ref "Q17") (pin "3") (pintype "output"))
      (node (ref "Q52") (pin "2") (pinfunction "G_2") (pintype "passive"))
      (node (ref "Q54") (pin "2") (pinfunction "G_2") (pintype "passive"))
    )
    (net (code "29") (name "/Left_IGN_8-") (class "Default")
      (node (ref "Q31") (pin "6") (pintype "output"))
      (node (ref "Q53") (pin "2") (pinfunction "G_2") (pintype "passive"))
      (node (ref "Q55") (pin "2") (pinfunction "G_2") (pintype "passive"))
    )
    (net (code "30") (name "/Left_NEG_D4") (class "Default") (node (ref "Q2") (pin "15") (pintype "input")))
    (net (code "31") (name "/Left_NEG_D5") (class "Default")
      (node (ref "Q2") (pin "12") (pintype "input"))
      (node (ref "Q2") (pin "14") (pintype "input"))
    )
    (net (code "32") (name "/Left_NEG_D6") (class "Default") (node (ref "Q2") (pin "13") (pintype "input")))
    (net (code "33") (name "/Left_NEG_NOT_0") (class "Default")
      (node (ref "Q17") (pin "4") (pintype "input"))
      (node (ref "Q6") (pin "8") (pintype "output"))
    )
    (net (code "34") (name "/Left_NEG_NOT_1") (class "Default")
      (node (ref "Q17") (pin "13") (pintype "input"))
      (node (ref "Q6") (pin "10") (pintype "output"))
    )
    (net (code "35") (name "/Left_NEG_NOT_2") (class "Default")
      (node (ref "Q17") (pin "10") (pintype "input"))
      (node (ref "Q6") (pin "12") (pintype "output"))
    )
    (net (code "36") (name "/Left_NEG_NOT_3") (class "Default")
      (node (ref "Q30") (pin "1") (pintype "input"))
      (node (ref "Q7") (pin "2") (pintype "output"))
    )
    (net (code "37") (name "/Left_NEG_NOT_4") (class "Default")
      (node (ref "Q30") (pin "4") (pintype "input"))
      (node (ref "Q7") (pin "4") (pintype "output"))
    )
    (net (code "38") (name "/Left_NEG_NOT_5") (class "Default")
      (node (ref "Q30") (pin "13") (pintype "input"))
      (node (ref "Q7") (pin "6") (pintype "output"))
    )
    (net (code "39") (name "/Left_NEG_NOT_6") (class "Default")
      (node (ref "Q30") (pin "10") (pintype "input"))
      (node (ref "Q7") (pin "8") (pintype "output"))
    )
    (net (code "40") (name "/Left_NEG_NOT_7") (class "Default")
      (node (ref "Q31") (pin "1") (pintype "input"))
      (node (ref "Q7") (pin "10") (pintype "output"))
    )
    (net (code "41") (name "/Left_NEG_NOT_8") (class "Default")
      (node (ref "Q31") (pin "4") (pintype "input"))
      (node (ref "Q7") (pin "12") (pintype "output"))
    )
    (net (code "42") (name "/Left_NEG_Signal_0") (class "Default")
      (node (ref "Q2") (pin "1") (pintype "output"))
      (node (ref "Q6") (pin "9") (pintype "input"))
    )
    (net (code "43") (name "/Left_NEG_Signal_1") (class "Default")
      (node (ref "Q2") (pin "2") (pintype "output"))
      (node (ref "Q6") (pin "11") (pintype "input"))
    )
    (net (code "44") (name "/Left_NEG_Signal_2") (class "Default")
      (node (ref "Q2") (pin "3") (pintype "output"))
      (node (ref "Q6") (pin "13") (pintype "input"))
    )
    (net (code "45") (name "/Left_NEG_Signal_3") (class "Default")
      (node (ref "Q2") (pin "4") (pintype "output"))
      (node (ref "Q7") (pin "1") (pintype "input"))
    )
    (net (code "46") (name "/Left_NEG_Signal_4") (class "Default")
      (node (ref "Q2") (pin "5") (pintype "output"))
      (node (ref "Q7") (pin "3") (pintype "input"))
    )
    (net (code "47") (name "/Left_NEG_Signal_5") (class "Default")
      (node (ref "Q2") (pin "6") (pintype "output"))
      (node (ref "Q7") (pin "5") (pintype "input"))
    )
    (net (code "48") (name "/Left_NEG_Signal_6") (class "Default")
      (node (ref "Q2") (pin "7") (pintype "output"))
      (node (ref "Q7") (pin "9") (pintype "input"))
    )
    (net (code "49") (name "/Left_NEG_Signal_7") (class "Default")
      (node (ref "Q2") (pin "9") (pintype "output"))
      (node (ref "Q7") (pin "11") (pintype "input"))
    )
    (net (code "50") (name "/Left_NEG_Signal_8") (class "Default")
      (node (ref "Q2") (pin "10") (pintype "output"))
      (node (ref "Q7") (pin "13") (pintype "input"))
    )
    (net (code "51") (name "/Left_POS_D0") (class "Default") (node (ref "Q1") (pin "15") (pintype "input")))
    (net (code "52") (name "/Left_POS_D1") (class "Default") (node (ref "Q1") (pin "14") (pintype "input")))
    (net (code "53") (name "/Left_POS_D2") (class "Default") (node (ref "Q1") (pin "13") (pintype "input")))
    (net (code "54") (name "/Left_POS_D3") (class "Default") (node (ref "Q1") (pin "12") (pintype "input")))
    (net (code "55") (name "/Left_POS_NOT_0") (class "Default")
      (node (ref "Q15") (pin "1") (pintype "input"))
      (node (ref "Q5") (pin "2") (pintype "output"))
    )
    (net (code "56") (name "/Left_POS_NOT_1") (class "Default")
      (node (ref "Q15") (pin "4") (pintype "input"))
      (node (ref "Q5") (pin "4") (pintype "output"))
    )
    (net (code "57") (name "/Left_POS_NOT_2") (class "Default")
      (node (ref "Q15") (pin "13") (pintype "input"))
      (node (ref "Q5") (pin "6") (pintype "output"))
    )
    (net (code "58") (name "/Left_POS_NOT_3") (class "Default")
      (node (ref "Q15") (pin "10") (pintype "input"))
      (node (ref "Q5") (pin "8") (pintype "output"))
    )
    (net (code "59") (name "/Left_POS_NOT_4") (class "Default")
      (node (ref "Q16") (pin "1") (pintype "input"))
      (node (ref "Q5") (pin "10") (pintype "output"))
    )
    (net (code "60") (name "/Left_POS_NOT_5") (class "Default")
      (node (ref "Q16") (pin "4") (pintype "input"))
      (node (ref "Q5") (pin "12") (pintype "output"))
    )
    (net (code "61") (name "/Left_POS_NOT_6") (class "Default")
      (node (ref "Q16") (pin "13") (pintype "input"))
      (node (ref "Q6") (pin "2") (pintype "output"))
    )
    (net (code "62") (name "/Left_POS_NOT_7") (class "Default")
      (node (ref "Q16") (pin "10") (pintype "input"))
      (node (ref "Q6") (pin "4") (pintype "output"))
    )
    (net (code "63") (name "/Left_POS_NOT_8") (class "Default")
      (node (ref "Q17") (pin "1") (pintype "input"))
      (node (ref "Q6") (pin "6") (pintype "output"))
    )
    (net (code "64") (name "/Left_POS_Signal_0") (class "Default")
      (node (ref "Q1") (pin "1") (pintype "output"))
      (node (ref "Q5") (pin "1") (pintype "input"))
    )
    (net (code "65") (name "/Left_POS_Signal_1") (class "Default")
      (node (ref "Q1") (pin "2") (pintype "output"))
      (node (ref "Q5") (pin "3") (pintype "input"))
    )
    (net (code "66") (name "/Left_POS_Signal_2") (class "Default")
      (node (ref "Q1") (pin "3") (pintype "output"))
      (node (ref "Q5") (pin "5") (pintype "input"))
    )
    (net (code "67") (name "/Left_POS_Signal_3") (class "Default")
      (node (ref "Q1") (pin "4") (pintype "output"))
      (node (ref "Q5") (pin "9") (pintype "input"))
    )
    (net (code "68") (name "/Left_POS_Signal_4") (class "Default")
      (node (ref "Q1") (pin "5") (pintype "output"))
      (node (ref "Q5") (pin "11") (pintype "input"))
    )
    (net (code "69") (name "/Left_POS_Signal_5") (class "Default")
      (node (ref "Q1") (pin "6") (pintype "output"))
      (node (ref "Q5") (pin "13") (pintype "input"))
    )
    (net (code "70") (name "/Left_POS_Signal_6") (class "Default")
      (node (ref "Q1") (pin "7") (pintype "output"))
      (node (ref "Q6") (pin "1") (pintype "input"))
    )
    (net (code "71") (name "/Left_POS_Signal_7") (class "Default")
      (node (ref "Q1") (pin "9") (pintype "output"))
      (node (ref "Q6") (pin "3") (pintype "input"))
    )
    (net (code "72") (name "/Left_POS_Signal_8") (class "Default")
      (node (ref "Q1") (pin "10") (pintype "output"))
      (node (ref "Q6") (pin "5") (pintype "input"))
    )
    (net (code "73") (name "/PWM") (class "Default")
      (node (ref "Q15") (pin "12") (pintype "input"))
      (node (ref "Q15") (pin "2") (pintype "input"))
      (node (ref "Q15") (pin "5") (pintype "input"))
      (node (ref "Q15") (pin "9") (pintype "input"))
      (node (ref "Q16") (pin "12") (pintype "input"))
      (node (ref "Q16") (pin "2") (pintype "input"))
      (node (ref "Q16") (pin "5") (pintype "input"))
      (node (ref "Q16") (pin "9") (pintype "input"))
      (node (ref "Q17") (pin "12") (pintype "input"))
      (node (ref "Q17") (pin "2") (pintype "input"))
      (node (ref "Q17") (pin "5") (pintype "input"))
      (node (ref "Q17") (pin "9") (pintype "input"))
      (node (ref "Q30") (pin "12") (pintype "input"))
      (node (ref "Q30") (pin "2") (pintype "input"))
      (node (ref "Q30") (pin "5") (pintype "input"))
      (node (ref "Q30") (pin "9") (pintype "input"))
      (node (ref "Q31") (pin "12") (pintype "input"))
      (node (ref "Q31") (pin "2") (pintype "input"))
      (node (ref "Q31") (pin "5") (pintype "input"))
      (node (ref "Q31") (pin "9") (pintype "input"))
      (node (ref "Q32") (pin "12") (pintype "input"))
      (node (ref "Q32") (pin "2") (pintype "input"))
      (node (ref "Q32") (pin "5") (pintype "input"))
      (node (ref "Q32") (pin "9") (pintype "input"))
      (node (ref "Q45") (pin "12") (pintype "input"))
      (node (ref "Q45") (pin "2") (pintype "input"))
      (node (ref "Q45") (pin "5") (pintype "input"))
      (node (ref "Q45") (pin "9") (pintype "input"))
      (node (ref "Q46") (pin "12") (pintype "input"))
      (node (ref "Q46") (pin "2") (pintype "input"))
      (node (ref "Q46") (pin "5") (pintype "input"))
      (node (ref "Q46") (pin "9") (pintype "input"))
      (node (ref "Q47") (pin "12") (pintype "input"))
      (node (ref "Q47") (pin "2") (pintype "input"))
      (node (ref "Q47") (pin "5") (pintype "input"))
      (node (ref "Q47") (pin "9") (pintype "input"))
    )
    (net (code "83") (name "/Right_IGN_0+") (class "Default")
      (node (ref "Q31") (pin "11") (pintype "output"))
    )
    (net (code "84") (name "/Right_IGN_0-") (class "Default") (node (ref "Q45") (pin "8") (pintype "output")))
    (net (code "85") (name "/Right_IGN_1+") (class "Default") (node (ref "Q31") (pin "8") (pintype "output")))
    (net (code "86") (name "/Right_IGN_1-") (class "Default") (node (ref "Q46") (pin "3") (pintype "output")))
    (net (code "87") (name "/Right_IGN_2+") (class "Default") (node (ref "Q32") (pin "3") (pintype "output")))
    (net (code "88") (name "/Right_IGN_2-") (class "Default") (node (ref "Q46") (pin "6") (pintype "output")))
    (net (code "89") (name "/Right_IGN_3+") (class "Default") (node (ref "Q32") (pin "6") (pintype "output")))
    (net (code "90") (name "/Right_IGN_3-") (class "Default")
      (node (ref "Q46") (pin "11") (pintype "output"))
    )
    (net (code "91") (name "/Right_IGN_4+") (class "Default")
      (node (ref "Q32") (pin "11") (pintype "output"))
    )
    (net (code "92") (name "/Right_IGN_4-") (class "Default") (node (ref "Q46") (pin "8") (pintype "output")))
    (net (code "93") (name "/Right_IGN_5+") (class "Default") (node (ref "Q32") (pin "8") (pintype "output")))
    (net (code "94") (name "/Right_IGN_5-") (class "Default") (node (ref "Q47") (pin "3") (pintype "output")))
    (net (code "95") (name "/Right_IGN_6+") (class "Default") (node (ref "Q45") (pin "3") (pintype "output")))
    (net (code "96") (name "/Right_IGN_6-") (class "Default") (node (ref "Q47") (pin "6") (pintype "output")))
    (net (code "97") (name "/Right_IGN_7+") (class "Default") (node (ref "Q45") (pin "6") (pintype "output")))
    (net (code "98") (name "/Right_IGN_7-") (class "Default")
      (node (ref "Q47") (pin "11") (pintype "output"))
    )
    (net (code "99") (name "/Right_IGN_8+") (class "Default")
      (node (ref "Q45") (pin "11") (pintype "output"))
    )
    (net (code "100") (name "/Right_IGN_8-") (class "Default")
      (node (ref "Q47") (pin "8") (pintype "output"))
    )
    (net (code "101") (name "/Right_NEG_A0") (class "Default") (node (ref "Q4") (pin "14") (pintype "input")))
    (net (code "102") (name "/Right_NEG_A1") (class "Default") (node (ref "Q4") (pin "13") (pintype "input")))
    (net (code "103") (name "/Right_NEG_A2") (class "Default") (node (ref "Q4") (pin "12") (pintype "input")))
    (net (code "104") (name "/Right_NEG_D13") (class "Default")
      (node (ref "Q4") (pin "15") (pintype "input"))
    )
    (net (code "105") (name "/Right_NEG_NOT_0") (class "Default")
      (node (ref "Q45") (pin "10") (pintype "input"))
      (node (ref "Q9") (pin "8") (pintype "output"))
    )
    (net (code "106") (name "/Right_NEG_NOT_1") (class "Default")
      (node (ref "Q46") (pin "1") (pintype "input"))
      (node (ref "Q9") (pin "10") (pintype "output"))
    )
    (net (code "107") (name "/Right_NEG_NOT_2") (class "Default")
      (node (ref "Q46") (pin "4") (pintype "input"))
      (node (ref "Q9") (pin "12") (pintype "output"))
    )
    (net (code "108") (name "/Right_NEG_NOT_3") (class "Default")
      (node (ref "Q10") (pin "2") (pintype "output"))
      (node (ref "Q46") (pin "13") (pintype "input"))
    )
    (net (code "109") (name "/Right_NEG_NOT_4") (class "Default")
      (node (ref "Q10") (pin "4") (pintype "output"))
      (node (ref "Q46") (pin "10") (pintype "input"))
    )
    (net (code "110") (name "/Right_NEG_NOT_5") (class "Default")
      (node (ref "Q10") (pin "6") (pintype "output"))
      (node (ref "Q47") (pin "1") (pintype "input"))
    )
    (net (code "111") (name "/Right_NEG_NOT_6") (class "Default")
      (node (ref "Q10") (pin "8") (pintype "output"))
      (node (ref "Q47") (pin "4") (pintype "input"))
    )
    (net (code "112") (name "/Right_NEG_NOT_7") (class "Default")
      (node (ref "Q10") (pin "10") (pintype "output"))
      (node (ref "Q47") (pin "13") (pintype "input"))
    )
    (net (code "113") (name "/Right_NEG_NOT_8") (class "Default")
      (node (ref "Q10") (pin "12") (pintype "output"))
      (node (ref "Q47") (pin "10") (pintype "input"))
    )
    (net (code "114") (name "/Right_NEG_Signal_0") (class "Default")
      (node (ref "Q4") (pin "1") (pintype "output"))
      (node (ref "Q9") (pin "9") (pintype "input"))
    )
    (net (code "115") (name "/Right_NEG_Signal_1") (class "Default")
      (node (ref "Q4") (pin "2") (pintype "output"))
      (node (ref "Q9") (pin "11") (pintype "input"))
    )
    (net (code "116") (name "/Right_NEG_Signal_2") (class "Default")
      (node (ref "Q4") (pin "3") (pintype "output"))
      (node (ref "Q9") (pin "13") (pintype "input"))
    )
    (net (code "117") (name "/Right_NEG_Signal_3") (class "Default")
      (node (ref "Q10") (pin "1") (pintype "input"))
      (node (ref "Q4") (pin "4") (pintype "output"))
    )
    (net (code "118") (name "/Right_NEG_Signal_4") (class "Default")
      (node (ref "Q10") (pin "3") (pintype "input"))
      (node (ref "Q4") (pin "5") (pintype "output"))
    )
    (net (code "119") (name "/Right_NEG_Signal_5") (class "Default")
      (node (ref "Q10") (pin "5") (pintype "input"))
      (node (ref "Q4") (pin "6") (pintype "output"))
    )
    (net (code "120") (name "/Right_NEG_Signal_6") (class "Default")
      (node (ref "Q10") (pin "9") (pintype "input"))
      (node (ref "Q4") (pin "7") (pintype "output"))
    )
    (net (code "121") (name "/Right_NEG_Signal_7") (class "Default")
      (node (ref "Q10") (pin "11") (pintype "input"))
      (node (ref "Q4") (pin "9") (pintype "output"))
    )
    (net (code "122") (name "/Right_NEG_Signal_8") (class "Default")
      (node (ref "Q10") (pin "13") (pintype "input"))
      (node (ref "Q4") (pin "10") (pintype "output"))
    )
    (net (code "123") (name "/Right_POS_D8") (class "Default") (node (ref "Q3") (pin "15") (pintype "input")))
    (net (code "124") (name "/Right_POS_D9") (class "Default") (node (ref "Q3") (pin "14") (pintype "input")))
    (net (code "125") (name "/Right_POS_D10") (class "Default")
      (node (ref "Q3") (pin "13") (pintype "input"))
    )
    (net (code "126") (name "/Right_POS_D11") (class "Default")
      (node (ref "Q3") (pin "12") (pintype "input"))
    )
    (net (code "127") (name "/Right_POS_NOT_0") (class "Default")
      (node (ref "Q31") (pin "13") (pintype "input"))
      (node (ref "Q8") (pin "2") (pintype "output"))
    )
    (net (code "128") (name "/Right_POS_NOT_1") (class "Default")
      (node (ref "Q31") (pin "10") (pintype "input"))
      (node (ref "Q8") (pin "4") (pintype "output"))
    )
    (net (code "129") (name "/Right_POS_NOT_2") (class "Default")
      (node (ref "Q32") (pin "1") (pintype "input"))
      (node (ref "Q8") (pin "6") (pintype "output"))
    )
    (net (code "130") (name "/Right_POS_NOT_3") (class "Default")
      (node (ref "Q32") (pin "4") (pintype "input"))
      (node (ref "Q8") (pin "8") (pintype "output"))
    )
    (net (code "131") (name "/Right_POS_NOT_4") (class "Default")
      (node (ref "Q32") (pin "13") (pintype "input"))
      (node (ref "Q8") (pin "10") (pintype "output"))
    )
    (net (code "132") (name "/Right_POS_NOT_5") (class "Default")
      (node (ref "Q32") (pin "10") (pintype "input"))
      (node (ref "Q8") (pin "12") (pintype "output"))
    )
    (net (code "133") (name "/Right_POS_NOT_6") (class "Default")
      (node (ref "Q45") (pin "1") (pintype "input"))
      (node (ref "Q9") (pin "2") (pintype "output"))
    )
    (net (code "134") (name "/Right_POS_NOT_7") (class "Default")
      (node (ref "Q45") (pin "4") (pintype "input"))
      (node (ref "Q9") (pin "4") (pintype "output"))
    )
    (net (code "135") (name "/Right_POS_NOT_8") (class "Default")
      (node (ref "Q45") (pin "13") (pintype "input"))
      (node (ref "Q9") (pin "6") (pintype "output"))
    )
    (net (code "136") (name "/Right_POS_Signal_0") (class "Default")
      (node (ref "Q3") (pin "1") (pintype "output"))
      (node (ref "Q8") (pin "1") (pintype "input"))
    )
    (net (code "137") (name "/Right_POS_Signal_1") (class "Default")
      (node (ref "Q3") (pin "2") (pintype "output"))
      (node (ref "Q8") (pin "3") (pintype "input"))
    )
    (net (code "138") (name "/Right_POS_Signal_2") (class "Default")
      (node (ref "Q3") (pin "3") (pintype "output"))
      (node (ref "Q8") (pin "5") (pintype "input"))
    )
    (net (code "139") (name "/Right_POS_Signal_3") (class "Default")
      (node (ref "Q3") (pin "4") (pintype "output"))
      (node (ref "Q8") (pin "9") (pintype "input"))
    )
    (net (code "140") (name "/Right_POS_Signal_4") (class "Default")
      (node (ref "Q3") (pin "5") (pintype "output"))
      (node (ref "Q8") (pin "11") (pintype "input"))
    )
    (net (code "141") (name "/Right_POS_Signal_5") (class "Default")
      (node (ref "Q3") (pin "6") (pintype "output"))
      (node (ref "Q8") (pin "13") (pintype "input"))
    )
    (net (code "142") (name "/Right_POS_Signal_6") (class "Default")
      (node (ref "Q3") (pin "7") (pintype "output"))
      (node (ref "Q9") (pin "1") (pintype "input"))
    )
    (net (code "143") (name "/Right_POS_Signal_7") (class "Default")
      (node (ref "Q3") (pin "9") (pintype "output"))
      (node (ref "Q9") (pin "3") (pintype "input"))
    )
    (net (code "144") (name "/Right_POS_Signal_8") (class "Default")
      (node (ref "Q3") (pin "10") (pintype "output"))
      (node (ref "Q9") (pin "5") (pintype "input"))
    )
    (net (code "147") (name "5V_PS") (class "Default")
      (node (ref "Q1") (pin "16") (pintype "power_in"))
      (node (ref "Q10") (pin "14") (pintype "power_in"))
      (node (ref "Q11") (pin "3") (pinfunction "D_3") (pintype "passive"))
      (node (ref "Q13") (pin "3") (pinfunction "D_3") (pintype "passive"))
      (node (ref "Q15") (pin "14") (pintype "power_in"))
      (node (ref "Q16") (pin "14") (pintype "power_in"))
      (node (ref "Q17") (pin "14") (pintype "power_in"))
      (node (ref "Q18") (pin "3") (pinfunction "D_3") (pintype "passive"))
      (node (ref "Q2") (pin "16") (pintype "power_in"))
      (node (ref "Q20") (pin "3") (pinfunction "D_3") (pintype "passive"))
      (node (ref "Q22") (pin "3") (pinfunction "D_3") (pintype "passive"))
      (node (ref "Q24") (pin "3") (pinfunction "D_3") (pintype "passive"))
      (node (ref "Q26") (pin "3") (pinfunction "D_3") (pintype "passive"))
      (node (ref "Q28") (pin "3") (pinfunction "D_3") (pintype "passive"))
      (node (ref "Q3") (pin "16") (pintype "power_in"))
      (node (ref "Q30") (pin "14") (pintype "power_in"))
      (node (ref "Q31") (pin "14") (pintype "power_in"))
      (node (ref "Q32") (pin "14") (pintype "power_in"))
      (node (ref "Q33") (pin "3") (pinfunction "D_3") (pintype "passive"))
      (node (ref "Q35") (pin "3") (pinfunction "D_3") (pintype "passive"))
      (node (ref "Q37") (pin "3") (pinfunction "D_3") (pintype "passive"))
      (node (ref "Q39") (pin "3") (pinfunction "D_3") (pintype "passive"))
      (node (ref "Q4") (pin "16") (pintype "power_in"))
      (node (ref "Q41") (pin "3") (pinfunction "D_3") (pintype "passive"))
      (node (ref "Q43") (pin "3") (pinfunction "D_3") (pintype "passive"))
      (node (ref "Q45") (pin "14") (pintype "power_in"))
      (node (ref "Q46") (pin "14") (pintype "power_in"))
      (node (ref "Q47") (pin "14") (pintype "power_in"))
      (node (ref "Q48") (pin "3") (pinfunction "D_3") (pintype "passive"))
      (node (ref "Q5") (pin "14") (pintype "power_in"))
      (node (ref "Q50") (pin "3") (pinfunction "D_3") (pintype "passive"))
      (node (ref "Q52") (pin "3") (pinfunction "D_3") (pintype "passive"))
      (node (ref "Q54") (pin "3") (pinfunction "D_3") (pintype "passive"))
      (node (ref "Q6") (pin "14") (pintype "power_in"))
      (node (ref "Q7") (pin "14") (pintype "power_in"))
      (node (ref "Q8") (pin "14") (pintype "power_in"))
      (node (ref "Q9") (pin "14") (pintype "power_in"))
    )
    (net (code "148") (name "GND") (class "Default")
      (node (ref "Q1") (pin "8") (pintype "power_in"))
      (node (ref "Q10") (pin "7") (pintype "power_in"))
      (node (ref "Q12") (pin "1") (pinfunction "S_1") (pintype "passive"))
      (node (ref "Q14") (pin "1") (pinfunction "S_1") (pintype "passive"))
      (node (ref "Q15") (pin "7") (pintype "power_in"))
      (node (ref "Q16") (pin "7") (pintype "power_in"))
      (node (ref "Q17") (pin "7") (pintype "power_in"))
      (node (ref "Q19") (pin "1") (pinfunction "S_1") (pintype "passive"))
      (node (ref "Q2") (pin "8") (pintype "power_in"))
      (node (ref "Q21") (pin "1") (pinfunction "S_1") (pintype "passive"))
      (node (ref "Q23") (pin "1") (pinfunction "S_1") (pintype "passive"))
      (node (ref "Q25") (pin "1") (pinfunction "S_1") (pintype "passive"))
      (node (ref "Q27") (pin "1") (pinfunction "S_1") (pintype "passive"))
      (node (ref "Q29") (pin "1") (pinfunction "S_1") (pintype "passive"))
      (node (ref "Q3") (pin "8") (pintype "power_in"))
      (node (ref "Q30") (pin "7") (pintype "power_in"))
      (node (ref "Q31") (pin "7") (pintype "power_in"))
      (node (ref "Q32") (pin "7") (pintype "power_in"))
      (node (ref "Q34") (pin "1") (pinfunction "S_1") (pintype "passive"))
      (node (ref "Q36") (pin "1") (pinfunction "S_1") (pintype "passive"))
      (node (ref "Q38") (pin "1") (pinfunction "S_1") (pintype "passive"))
      (node (ref "Q4") (pin "8") (pintype "power_in"))
      (node (ref "Q40") (pin "1") (pinfunction "S_1") (pintype "passive"))
      (node (ref "Q42") (pin "1") (pinfunction "S_1") (pintype "passive"))
      (node (ref "Q44") (pin "1") (pinfunction "S_1") (pintype "passive"))
      (node (ref "Q45") (pin "7") (pintype "power_in"))
      (node (ref "Q46") (pin "7") (pintype "power_in"))
      (node (ref "Q47") (pin "7") (pintype "power_in"))
      (node (ref "Q49") (pin "1") (pinfunction "S_1") (pintype "passive"))
      (node (ref "Q5") (pin "7") (pintype "power_in"))
      (node (ref "Q51") (pin "1") (pinfunction "S_1") (pintype "passive"))
      (node (ref "Q53") (pin "1") (pinfunction "S_1") (pintype "passive"))
      (node (ref "Q55") (pin "1") (pinfunction "S_1") (pintype "passive"))
      (node (ref "Q6") (pin "7") (pintype "power_in"))
      (node (ref "Q7") (pin "7") (pintype "power_in"))
      (node (ref "Q8") (pin "7") (pintype "power_in"))
      (node (ref "Q9") (pin "7") (pintype "power_in"))
    )
    (net (code "149") (name "Net-(Q11-S)") (class "Default")
      (node (ref "Q11") (pin "1") (pinfunction "S_1") (pintype "passive"))
      (node (ref "R1") (pin "2") (pinfunction "2_2") (pintype "passive"))
    )
    (net (code "150") (name "Net-(Q13-S)") (class "Default")
      (node (ref "Q13") (pin "1") (pinfunction "S_1") (pintype "passive"))
      (node (ref "R2") (pin "2") (pinfunction "2_2") (pintype "passive"))
    )
    (net (code "151") (name "Net-(Q18-S)") (class "Default")
      (node (ref "Q18") (pin "1") (pinfunction "S_1") (pintype "passive"))
      (node (ref "R3") (pin "2") (pinfunction "2_2") (pintype "passive"))
    )
    (net (code "152") (name "Net-(Q20-S)") (class "Default")
      (node (ref "Q20") (pin "1") (pinfunction "S_1") (pintype "passive"))
      (node (ref "R4") (pin "2") (pinfunction "2_2") (pintype "passive"))
    )
    (net (code "153") (name "Net-(Q22-S)") (class "Default")
      (node (ref "Q22") (pin "1") (pinfunction "S_1") (pintype "passive"))
      (node (ref "R5") (pin "2") (pinfunction "2_2") (pintype "passive"))
    )
    (net (code "154") (name "Net-(Q24-S)") (class "Default")
      (node (ref "Q24") (pin "1") (pinfunction "S_1") (pintype "passive"))
      (node (ref "R6") (pin "2") (pinfunction "2_2") (pintype "passive"))
    )
    (net (code "155") (name "Net-(Q26-S)") (class "Default")
      (node (ref "Q26") (pin "1") (pinfunction "S_1") (pintype "passive"))
      (node (ref "R7") (pin "2") (pinfunction "2_2") (pintype "passive"))
    )
    (net (code "156") (name "Net-(Q28-S)") (class "Default")
      (node (ref "Q28") (pin "1") (pinfunction "S_1") (pintype "passive"))
      (node (ref "R8") (pin "2") (pinfunction "2_2") (pintype "passive"))
    )
    (net (code "157") (name "Net-(Q33-S)") (class "Default")
      (node (ref "Q33") (pin "1") (pinfunction "S_1") (pintype "passive"))
      (node (ref "R9") (pin "2") (pinfunction "2_2") (pintype "passive"))
    )
    (net (code "158") (name "Net-(Q35-S)") (class "Default")
      (node (ref "Q35") (pin "1") (pinfunction "S_1") (pintype "passive"))
      (node (ref "R10") (pin "2") (pinfunction "2_2") (pintype "passive"))
    )
    (net (code "159") (name "Net-(Q37-S)") (class "Default")
      (node (ref "Q37") (pin "1") (pinfunction "S_1") (pintype "passive"))
      (node (ref "R11") (pin "2") (pinfunction "2_2") (pintype "passive"))
    )
    (net (code "160") (name "Net-(Q39-S)") (class "Default")
      (node (ref "Q39") (pin "1") (pinfunction "S_1") (pintype "passive"))
      (node (ref "R12") (pin "2") (pinfunction "2_2") (pintype "passive"))
    )
    (net (code "161") (name "Net-(Q41-S)") (class "Default")
      (node (ref "Q41") (pin "1") (pinfunction "S_1") (pintype "passive"))
      (node (ref "R13") (pin "2") (pinfunction "2_2") (pintype "passive"))
    )
    (net (code "162") (name "Net-(Q43-S)") (class "Default")
      (node (ref "Q43") (pin "1") (pinfunction "S_1") (pintype "passive"))
      (node (ref "R14") (pin "2") (pinfunction "2_2") (pintype "passive"))
    )
    (net (code "163") (name "Net-(Q48-S)") (class "Default")
      (node (ref "Q48") (pin "1") (pinfunction "S_1") (pintype "passive"))
      (node (ref "R15") (pin "2") (pinfunction "2_2") (pintype "passive"))
    )
    (net (code "164") (name "Net-(Q50-S)") (class "Default")
      (node (ref "Q50") (pin "1") (pinfunction "S_1") (pintype "passive"))
      (node (ref "R16") (pin "2") (pinfunction "2_2") (pintype "passive"))
    )
    (net (code "165") (name "Net-(Q52-S)") (class "Default")
      (node (ref "Q52") (pin "1") (pinfunction "S_1") (pintype "passive"))
      (node (ref "R17") (pin "2") (pinfunction "2_2") (pintype "passive"))
    )
    (net (code "166") (name "Net-(Q54-S)") (class "Default")
      (node (ref "Q54") (pin "1") (pinfunction "S_1") (pintype "passive"))
      (node (ref "R18") (pin "2") (pinfunction "2_2") (pintype "passive"))
    )
    (net (code "167") (name "unconnected-(Q1-Pad11)") (class "Default")
      (node (ref "Q1") (pin "11") (pintype "output+no_connect"))
    )
    (net (code "168") (name "unconnected-(Q2-Pad11)") (class "Default")
      (node (ref "Q2") (pin "11") (pintype "output+no_connect"))
    )
    (net (code "169") (name "unconnected-(Q3-Pad11)") (class "Default")
      (node (ref "Q3") (pin "11") (pintype "output+no_connect"))
    )
    (net (code "170") (name "unconnected-(Q4-Pad11)") (class "Default")
      (node (ref "Q4") (pin "11") (pintype "output+no_connect"))
    )
  )
)
